# tick-mk-4_6_5.net
KiCad netlist of a schematic drawn in EAGLE
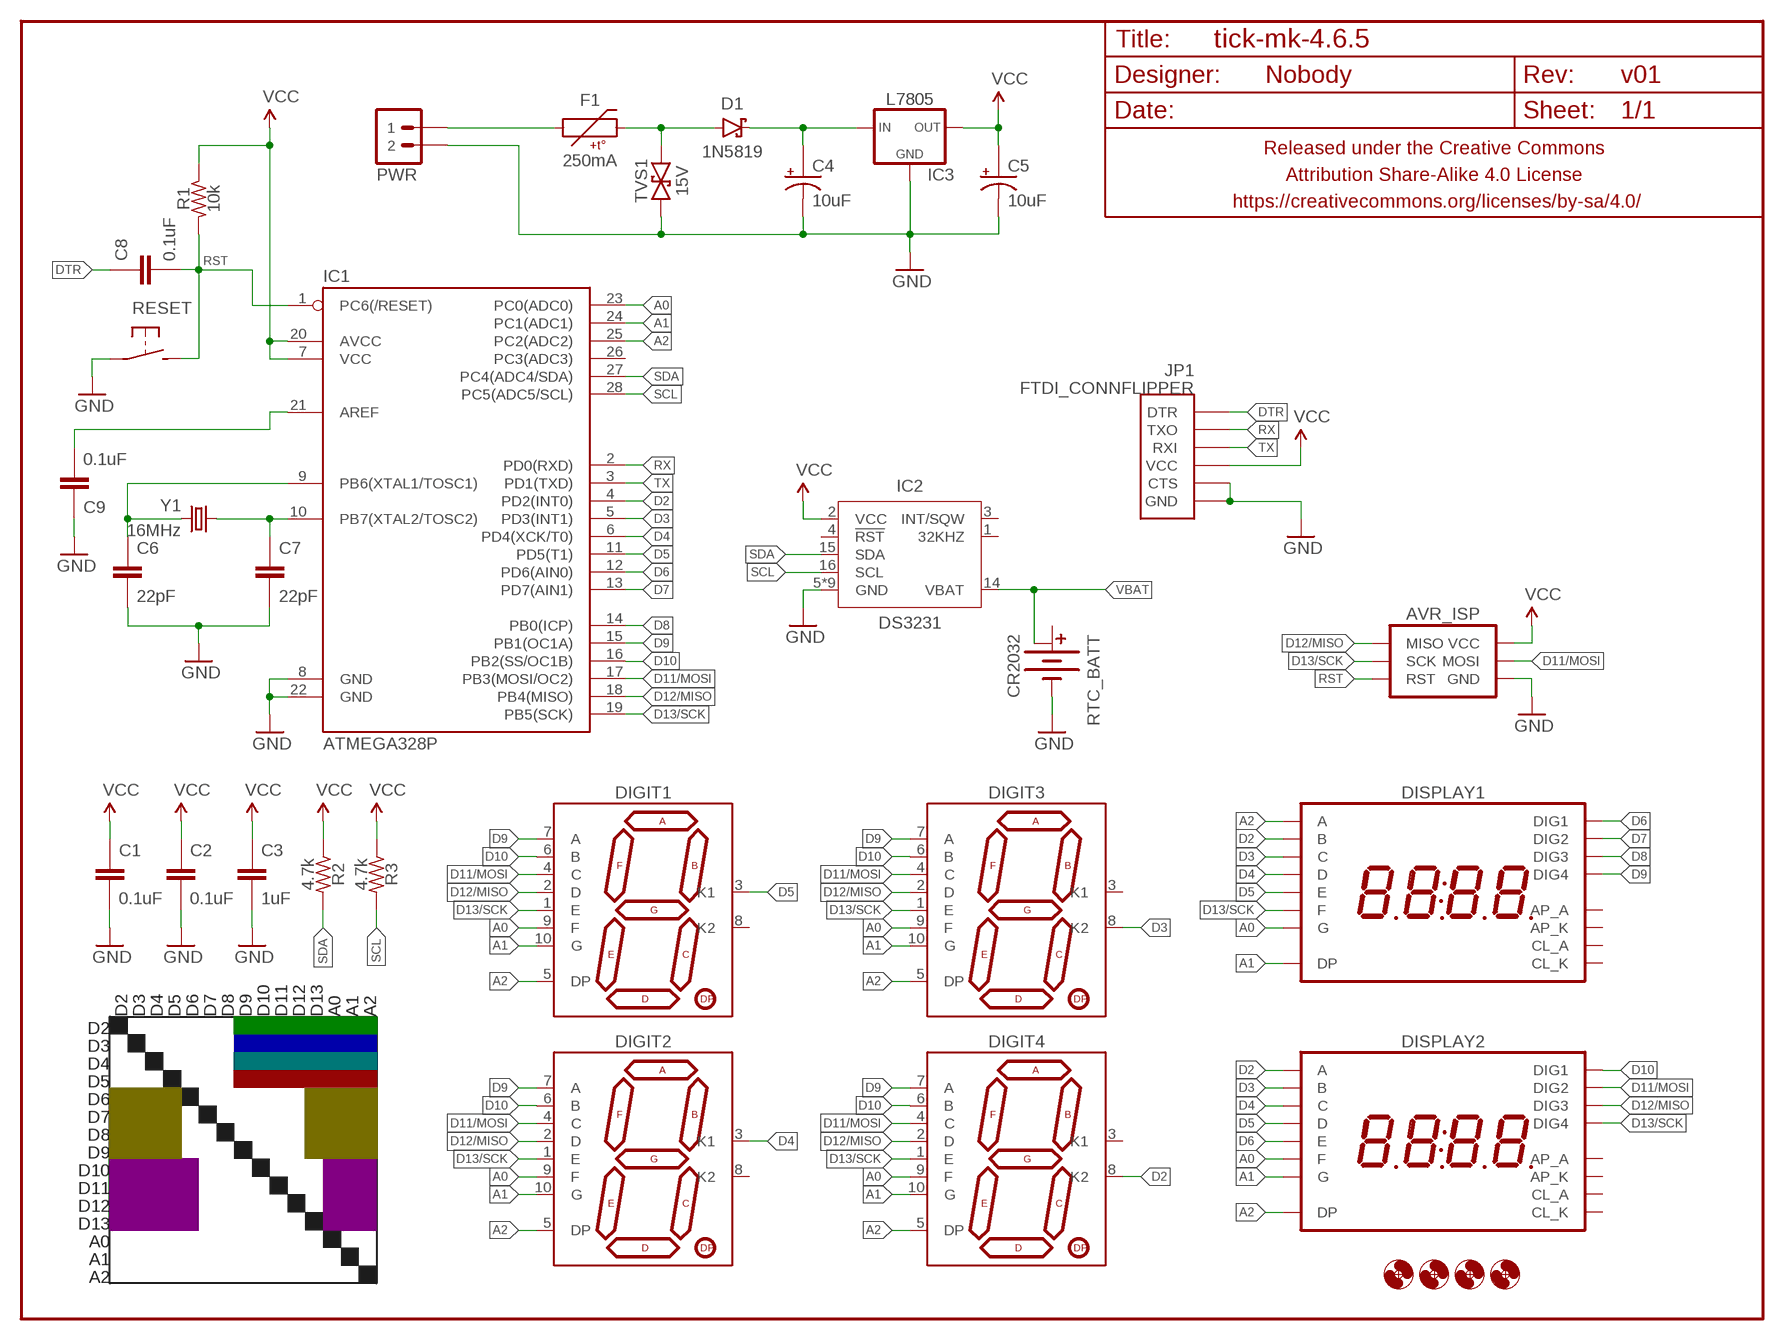
[diagram p0: schematic, sheet 1]

(export (version "E")
  (design (tool "Eeschema 10.0.6"))
  (components
    (comp (ref "AVR_ISP")
      (value "AVR_SPI_PRG_6PTH")
      (footprint "eagle-import:2X3")
      (libsource (lib "eagle-import") (part "AVR_SPI_PRG_6PTH"))
    )
    (comp (ref "C1")
      (value "0.1uF")
      (footprint "eagle-import:C025-024X044")
      (libsource (lib "eagle-import") (part "CAPACITOR-CERAMIC025-024X044"))
    )
    (comp (ref "C2")
      (value "0.1uF")
      (footprint "eagle-import:C025-024X044")
      (libsource (lib "eagle-import") (part "CAPACITOR-CERAMIC025-024X044"))
    )
    (comp (ref "C3")
      (value "1uF")
      (footprint "eagle-import:C025-024X044")
      (libsource (lib "eagle-import") (part "CAPACITOR-CERAMIC025-024X044"))
    )
    (comp (ref "C4")
      (value "10uF")
      (footprint "eagle-import:E2-5")
      (libsource (lib "eagle-import") (part "CAPACITOR-POLARIZEDE2-5"))
    )
    (comp (ref "C5")
      (value "10uF")
      (footprint "eagle-import:E2-5")
      (libsource (lib "eagle-import") (part "CAPACITOR-POLARIZEDE2-5"))
    )
    (comp (ref "C6")
      (value "22pF")
      (footprint "eagle-import:C025-024X044")
      (libsource (lib "eagle-import") (part "CAPACITOR-CERAMIC025-024X044"))
    )
    (comp (ref "C7")
      (value "22pF")
      (footprint "eagle-import:C025-024X044")
      (libsource (lib "eagle-import") (part "CAPACITOR-CERAMIC025-024X044"))
    )
    (comp (ref "C8")
      (value "0.1uF")
      (footprint "eagle-import:C025-024X044")
      (libsource (lib "eagle-import") (part "CAPACITOR-CERAMIC025-024X044"))
    )
    (comp (ref "C9")
      (value "0.1uF")
      (footprint "eagle-import:C025-024X044")
      (libsource (lib "eagle-import") (part "CAPACITOR-CERAMIC025-024X044"))
    )
    (comp (ref "D1")
      (value "1N5819")
      (footprint "eagle-import:DIODE-10.16MM")
      (libsource (lib "eagle-import") (part "DIODE-SCHOTTKYPTH-10.16MM"))
    )
    (comp (ref "DIGIT1")
      (value "7SEG_1DIGPTH-25.4MM-BARE")
      (footprint "eagle-import:7SEG_1DIG_25.4MM_NOSILK")
      (libsource (lib "eagle-import") (part "7SEG_1DIGPTH-25.4MM-BARE"))
    )
    (comp (ref "DIGIT2")
      (value "7SEG_1DIGPTH-25.4MM-BARE")
      (footprint "eagle-import:7SEG_1DIG_25.4MM_NOSILK")
      (libsource (lib "eagle-import") (part "7SEG_1DIGPTH-25.4MM-BARE"))
    )
    (comp (ref "DIGIT3")
      (value "7SEG_1DIGPTH-25.4MM-BARE")
      (footprint "eagle-import:7SEG_1DIG_25.4MM_NOSILK")
      (libsource (lib "eagle-import") (part "7SEG_1DIGPTH-25.4MM-BARE"))
    )
    (comp (ref "DIGIT4")
      (value "7SEG_1DIGPTH-25.4MM-BARE")
      (footprint "eagle-import:7SEG_1DIG_25.4MM_NOSILK")
      (libsource (lib "eagle-import") (part "7SEG_1DIGPTH-25.4MM-BARE"))
    )
    (comp (ref "DISPLAY1")
      (value "7SEG_4DIGIT_COLON_APOS")
      (footprint "eagle-import:7SEG_4DIG_10MM")
      (libsource (lib "eagle-import") (part "7SEG_4DIGIT_COLON_APOS"))
    )
    (comp (ref "DISPLAY2")
      (value "7SEG_4DIGIT_COLON_APOS")
      (footprint "eagle-import:7SEG_4DIG_10MM")
      (libsource (lib "eagle-import") (part "7SEG_4DIGIT_COLON_APOS"))
    )
    (comp (ref "F1")
      (value "250mA")
      (footprint "eagle-import:PTC-PTH-5.08MM")
      (libsource (lib "eagle-import") (part "PTCPTH-5.08MM"))
    )
    (comp (ref "FRAME1")
      (value "FRAME-LETTERNO_PACKAGE")
      (footprint "eagle-import:DUMMY")
      (fields (field (name "DESIGNER") "Nobody"))
      (libsource (lib "eagle-import") (part "FRAME-LETTERNO_PACKAGE"))
    )
    (comp (ref "H1")
      (value "HOLE#2")
      (footprint "eagle-import:HOLE-#2")
      (libsource (lib "eagle-import") (part "HOLE#2"))
    )
    (comp (ref "H2")
      (value "HOLE#2")
      (footprint "eagle-import:HOLE-#2")
      (libsource (lib "eagle-import") (part "HOLE#2"))
    )
    (comp (ref "H3")
      (value "HOLE#2")
      (footprint "eagle-import:HOLE-#2")
      (libsource (lib "eagle-import") (part "HOLE#2"))
    )
    (comp (ref "H4")
      (value "HOLE#2")
      (footprint "eagle-import:HOLE-#2")
      (libsource (lib "eagle-import") (part "HOLE#2"))
    )
    (comp (ref "IC1")
      (value "ATMEGA328P")
      (footprint "eagle-import:DIL28-3")
      (libsource (lib "eagle-import") (part "ATMEGA328P_PDIP"))
    )
    (comp (ref "IC2")
      (value "DS3231")
      (footprint "eagle-import:SO16W")
      (libsource (lib "eagle-import") (part "DS3231"))
    )
    (comp (ref "IC3")
      (value "L7805")
      (footprint "eagle-import:TO220-IGO-THERMPAD")
      (libsource (lib "eagle-import") (part "V_REG_78XXTO-220-THERMPAD"))
    )
    (comp (ref "JP1")
      (value "FTDI_CONNFLIPPER")
      (footprint "eagle-import:FTDI_CONN_FLIP")
      (libsource (lib "eagle-import") (part "FTDI_CONNFLIPPER"))
    )
    (comp (ref "PWR")
      (value "M02JST-PTH-VERT")
      (footprint "eagle-import:JST-2-PH-VERT-PTH")
      (libsource (lib "eagle-import") (part "M02JST-PTH-VERT"))
    )
    (comp (ref "R1")
      (value "10k")
      (footprint "eagle-import:RESISTOR-AXIAL-PTH-7.62MM")
      (libsource (lib "eagle-import") (part "RESISTORPTH-AXIAL-7.62MM"))
    )
    (comp (ref "R2")
      (value "4.7k")
      (footprint "eagle-import:RESISTOR-AXIAL-PTH-6.35MM")
      (libsource (lib "eagle-import") (part "RESISTORPTH-AXIAL-6.35MM"))
    )
    (comp (ref "R3")
      (value "4.7k")
      (footprint "eagle-import:RESISTOR-AXIAL-PTH-6.35MM")
      (libsource (lib "eagle-import") (part "RESISTORPTH-AXIAL-6.35MM"))
    )
    (comp (ref "RESET")
      (value "SPST-NO-TACT3MM-RA")
      (footprint "eagle-import:TACTILE-PTH-SIDE")
      (libsource (lib "eagle-import") (part "SPST-NO-TACT3MM-RA"))
    )
    (comp (ref "RTC_BATT")
      (value "CR2032")
      (footprint "eagle-import:BATTCON_20MM_MINE")
      (libsource (lib "eagle-import") (part "BATTERY-COINCR2032_SMD"))
    )
    (comp (ref "TVS1")
      (value "15V")
      (footprint "eagle-import:DO-41-TVS-BI-10.16MM")
      (libsource (lib "eagle-import") (part "TVSDO-41-10.16MM"))
    )
    (comp (ref "Y1")
      (value "16MHz")
      (footprint "eagle-import:HC49U-V")
      (libsource (lib "eagle-import") (part "CRYSTALHC49UV"))
    )
  )
  (nets
    (net (code "1") (name "A0") (class "Default")
      (node (ref "DIGIT1") (pin "9") (pinfunction "F_9") (pintype "bidirectional"))
      (node (ref "DIGIT2") (pin "9") (pinfunction "F_9") (pintype "bidirectional"))
      (node (ref "DIGIT3") (pin "9") (pinfunction "F_9") (pintype "bidirectional"))
      (node (ref "DIGIT4") (pin "9") (pinfunction "F_9") (pintype "bidirectional"))
      (node (ref "DISPLAY1") (pin "15") (pinfunction "G_15") (pintype "passive"))
      (node (ref "DISPLAY2") (pin "11") (pinfunction "F_11") (pintype "passive"))
      (node (ref "IC1") (pin "23") (pinfunction "PC0(ADC0)_23") (pintype "bidirectional"))
    )
    (net (code "2") (name "A1") (class "Default")
      (node (ref "DIGIT1") (pin "10") (pinfunction "G_10") (pintype "bidirectional"))
      (node (ref "DIGIT2") (pin "10") (pinfunction "G_10") (pintype "bidirectional"))
      (node (ref "DIGIT3") (pin "10") (pinfunction "G_10") (pintype "bidirectional"))
      (node (ref "DIGIT4") (pin "10") (pinfunction "G_10") (pintype "bidirectional"))
      (node (ref "DISPLAY1") (pin "7") (pinfunction "DP_7") (pintype "passive"))
      (node (ref "DISPLAY2") (pin "15") (pinfunction "G_15") (pintype "passive"))
      (node (ref "IC1") (pin "24") (pinfunction "PC1(ADC1)_24") (pintype "bidirectional"))
    )
    (net (code "3") (name "A2") (class "Default")
      (node (ref "DIGIT1") (pin "5") (pinfunction "DP_5") (pintype "bidirectional"))
      (node (ref "DIGIT2") (pin "5") (pinfunction "DP_5") (pintype "bidirectional"))
      (node (ref "DIGIT3") (pin "5") (pinfunction "DP_5") (pintype "bidirectional"))
      (node (ref "DIGIT4") (pin "5") (pinfunction "DP_5") (pintype "bidirectional"))
      (node (ref "DISPLAY1") (pin "14") (pinfunction "A_14") (pintype "passive"))
      (node (ref "DISPLAY2") (pin "7") (pinfunction "DP_7") (pintype "passive"))
      (node (ref "IC1") (pin "25") (pinfunction "PC2(ADC2)_25") (pintype "bidirectional"))
    )
    (net (code "4") (name "D2") (class "Default")
      (node (ref "DIGIT4") (pin "8") (pinfunction "K2_8") (pintype "bidirectional"))
      (node (ref "DISPLAY1") (pin "16") (pinfunction "B_16") (pintype "passive"))
      (node (ref "DISPLAY2") (pin "14") (pinfunction "A_14") (pintype "passive"))
      (node (ref "IC1") (pin "4") (pinfunction "PD2(INT0)_4") (pintype "bidirectional"))
    )
    (net (code "5") (name "D3") (class "Default")
      (node (ref "DIGIT3") (pin "8") (pinfunction "K2_8") (pintype "bidirectional"))
      (node (ref "DISPLAY1") (pin "13") (pinfunction "C_13") (pintype "passive"))
      (node (ref "DISPLAY2") (pin "16") (pinfunction "B_16") (pintype "passive"))
      (node (ref "IC1") (pin "5") (pinfunction "PD3(INT1)_5") (pintype "bidirectional"))
    )
    (net (code "6") (name "D4") (class "Default")
      (node (ref "DIGIT2") (pin "3") (pinfunction "K1_3") (pintype "bidirectional"))
      (node (ref "DISPLAY1") (pin "3") (pinfunction "D_3") (pintype "passive"))
      (node (ref "DISPLAY2") (pin "13") (pinfunction "C_13") (pintype "passive"))
      (node (ref "IC1") (pin "6") (pinfunction "PD4(XCK/T0)_6") (pintype "bidirectional"))
    )
    (net (code "7") (name "D5") (class "Default")
      (node (ref "DIGIT1") (pin "3") (pinfunction "K1_3") (pintype "bidirectional"))
      (node (ref "DISPLAY1") (pin "5") (pinfunction "E_5") (pintype "passive"))
      (node (ref "DISPLAY2") (pin "3") (pinfunction "D_3") (pintype "passive"))
      (node (ref "IC1") (pin "11") (pinfunction "PD5(T1)_11") (pintype "bidirectional"))
    )
    (net (code "8") (name "D6") (class "Default")
      (node (ref "DISPLAY1") (pin "1") (pinfunction "DIG1_1") (pintype "passive"))
      (node (ref "DISPLAY2") (pin "5") (pinfunction "E_5") (pintype "passive"))
      (node (ref "IC1") (pin "12") (pinfunction "PD6(AIN0)_12") (pintype "bidirectional"))
    )
    (net (code "9") (name "D7") (class "Default")
      (node (ref "DISPLAY1") (pin "2") (pinfunction "DIG2_2") (pintype "passive"))
      (node (ref "IC1") (pin "13") (pinfunction "PD7(AIN1)_13") (pintype "bidirectional"))
    )
    (net (code "10") (name "D8") (class "Default")
      (node (ref "DISPLAY1") (pin "6") (pinfunction "DIG3_6") (pintype "passive"))
      (node (ref "IC1") (pin "14") (pinfunction "PB0(ICP)_14") (pintype "bidirectional"))
    )
    (net (code "11") (name "D9") (class "Default")
      (node (ref "DIGIT1") (pin "7") (pinfunction "A_7") (pintype "bidirectional"))
      (node (ref "DIGIT2") (pin "7") (pinfunction "A_7") (pintype "bidirectional"))
      (node (ref "DIGIT3") (pin "7") (pinfunction "A_7") (pintype "bidirectional"))
      (node (ref "DIGIT4") (pin "7") (pinfunction "A_7") (pintype "bidirectional"))
      (node (ref "DISPLAY1") (pin "8") (pinfunction "DIG4_8") (pintype "passive"))
      (node (ref "IC1") (pin "15") (pinfunction "PB1(OC1A)_15") (pintype "bidirectional"))
    )
    (net (code "12") (name "D10") (class "Default")
      (node (ref "DIGIT1") (pin "6") (pinfunction "B_6") (pintype "bidirectional"))
      (node (ref "DIGIT2") (pin "6") (pinfunction "B_6") (pintype "bidirectional"))
      (node (ref "DIGIT3") (pin "6") (pinfunction "B_6") (pintype "bidirectional"))
      (node (ref "DIGIT4") (pin "6") (pinfunction "B_6") (pintype "bidirectional"))
      (node (ref "DISPLAY2") (pin "1") (pinfunction "DIG1_1") (pintype "passive"))
      (node (ref "IC1") (pin "16") (pinfunction "PB2(SS/OC1B)_16") (pintype "bidirectional"))
    )
    (net (code "13") (name "D11{slash}MOSI") (class "Default")
      (node (ref "AVR_ISP") (pin "4") (pinfunction "MOSI_4") (pintype "passive"))
      (node (ref "DIGIT1") (pin "4") (pinfunction "C_4") (pintype "bidirectional"))
      (node (ref "DIGIT2") (pin "4") (pinfunction "C_4") (pintype "bidirectional"))
      (node (ref "DIGIT3") (pin "4") (pinfunction "C_4") (pintype "bidirectional"))
      (node (ref "DIGIT4") (pin "4") (pinfunction "C_4") (pintype "bidirectional"))
      (node (ref "DISPLAY2") (pin "2") (pinfunction "DIG2_2") (pintype "passive"))
      (node (ref "IC1") (pin "17") (pinfunction "PB3(MOSI/OC2)_17") (pintype "bidirectional"))
    )
    (net (code "14") (name "D12{slash}MISO") (class "Default")
      (node (ref "AVR_ISP") (pin "1") (pinfunction "MISO_1") (pintype "passive"))
      (node (ref "DIGIT1") (pin "2") (pinfunction "D_2") (pintype "bidirectional"))
      (node (ref "DIGIT2") (pin "2") (pinfunction "D_2") (pintype "bidirectional"))
      (node (ref "DIGIT3") (pin "2") (pinfunction "D_2") (pintype "bidirectional"))
      (node (ref "DIGIT4") (pin "2") (pinfunction "D_2") (pintype "bidirectional"))
      (node (ref "DISPLAY2") (pin "6") (pinfunction "DIG3_6") (pintype "passive"))
      (node (ref "IC1") (pin "18") (pinfunction "PB4(MISO)_18") (pintype "bidirectional"))
    )
    (net (code "15") (name "D13{slash}SCK") (class "Default")
      (node (ref "AVR_ISP") (pin "3") (pinfunction "SCK_3") (pintype "passive"))
      (node (ref "DIGIT1") (pin "1") (pinfunction "E_1") (pintype "bidirectional"))
      (node (ref "DIGIT2") (pin "1") (pinfunction "E_1") (pintype "bidirectional"))
      (node (ref "DIGIT3") (pin "1") (pinfunction "E_1") (pintype "bidirectional"))
      (node (ref "DIGIT4") (pin "1") (pinfunction "E_1") (pintype "bidirectional"))
      (node (ref "DISPLAY1") (pin "11") (pinfunction "F_11") (pintype "passive"))
      (node (ref "DISPLAY2") (pin "8") (pinfunction "DIG4_8") (pintype "passive"))
      (node (ref "IC1") (pin "19") (pinfunction "PB5(SCK)_19") (pintype "bidirectional"))
    )
    (net (code "16") (name "DTR") (class "Default")
      (node (ref "C8") (pin "1") (pinfunction "1_1") (pintype "passive"))
      (node (ref "JP1") (pin "DTR") (pinfunction "DTR_DTR") (pintype "bidirectional"))
    )
    (net (code "17") (name "GND") (class "Default")
      (node (ref "AVR_ISP") (pin "6") (pinfunction "GND_6") (pintype "passive"))
      (node (ref "C1") (pin "2") (pinfunction "2_2") (pintype "passive"))
      (node (ref "C2") (pin "2") (pinfunction "2_2") (pintype "passive"))
      (node (ref "C3") (pin "2") (pinfunction "2_2") (pintype "passive"))
      (node (ref "C4") (pin "-") (pinfunction "-_-") (pintype "passive"))
      (node (ref "C5") (pin "-") (pinfunction "-_-") (pintype "passive"))
      (node (ref "C6") (pin "2") (pinfunction "2_2") (pintype "passive"))
      (node (ref "C7") (pin "2") (pinfunction "2_2") (pintype "passive"))
      (node (ref "C9") (pin "1") (pinfunction "1_1") (pintype "passive"))
      (node (ref "IC1") (pin "22") (pinfunction "GND_22") (pintype "bidirectional"))
      (node (ref "IC1") (pin "8") (pinfunction "GND_8") (pintype "bidirectional"))
      (node (ref "IC2") (pin "10") (pinfunction "GND_10") (pintype "bidirectional"))
      (node (ref "IC2") (pin "11") (pinfunction "GND_11") (pintype "bidirectional"))
      (node (ref "IC2") (pin "12") (pinfunction "GND_12") (pintype "bidirectional"))
      (node (ref "IC2") (pin "13") (pinfunction "GND_13") (pintype "bidirectional"))
      (node (ref "IC2") (pin "5") (pinfunction "GND_5") (pintype "bidirectional"))
      (node (ref "IC2") (pin "6") (pinfunction "GND_6") (pintype "bidirectional"))
      (node (ref "IC2") (pin "7") (pinfunction "GND_7") (pintype "bidirectional"))
      (node (ref "IC2") (pin "8") (pinfunction "GND_8") (pintype "bidirectional"))
      (node (ref "IC2") (pin "9") (pinfunction "GND_9") (pintype "bidirectional"))
      (node (ref "IC3") (pin "4") (pinfunction "GND_4") (pintype "bidirectional"))
      (node (ref "IC3") (pin "GND") (pinfunction "GND_GND") (pintype "bidirectional"))
      (node (ref "JP1") (pin "CTS") (pinfunction "CTS_CTS") (pintype "bidirectional"))
      (node (ref "JP1") (pin "GND") (pinfunction "GND_GND") (pintype "bidirectional"))
      (node (ref "PWR") (pin "2") (pinfunction "2_2") (pintype "passive"))
      (node (ref "RESET") (pin "1") (pinfunction "1_1") (pintype "passive"))
      (node (ref "RTC_BATT") (pin "BOTTOM") (pinfunction "-_BOTTOM") (pintype "bidirectional"))
      (node (ref "TVS1") (pin "P$1") (pinfunction "1_P$1") (pintype "passive"))
    )
    (net (code "18") (name "Net-(C4-Pad+)") (class "Default")
      (node (ref "C4") (pin "+") (pinfunction "+_+") (pintype "passive"))
      (node (ref "D1") (pin "C") (pinfunction "C_C") (pintype "passive"))
      (node (ref "IC3") (pin "IN") (pinfunction "IN_IN") (pintype "bidirectional"))
    )
    (net (code "19") (name "Net-(F1-1)") (class "Default")
      (node (ref "F1") (pin "P$1") (pinfunction "1_P$1") (pintype "passive"))
      (node (ref "PWR") (pin "1") (pinfunction "1_1") (pintype "passive"))
    )
    (net (code "20") (name "Net-(F1-2)") (class "Default")
      (node (ref "D1") (pin "A") (pinfunction "A_A") (pintype "passive"))
      (node (ref "F1") (pin "P$2") (pinfunction "2_P$2") (pintype "passive"))
      (node (ref "TVS1") (pin "P$2") (pinfunction "2_P$2") (pintype "passive"))
    )
    (net (code "21") (name "Net-(IC1-AREF)") (class "Default")
      (node (ref "C9") (pin "2") (pinfunction "2_2") (pintype "passive"))
      (node (ref "IC1") (pin "21") (pinfunction "AREF_21") (pintype "bidirectional"))
    )
    (net (code "22") (name "Net-(IC1-PB6(XTAL1{slash}TOSC1))") (class "Default")
      (node (ref "C6") (pin "1") (pinfunction "1_1") (pintype "passive"))
      (node (ref "IC1") (pin "9") (pinfunction "PB6(XTAL1/TOSC1)_9") (pintype "bidirectional"))
      (node (ref "Y1") (pin "2") (pinfunction "2_2") (pintype "passive"))
    )
    (net (code "23") (name "Net-(IC1-PB7(XTAL2{slash}TOSC2))") (class "Default")
      (node (ref "C7") (pin "1") (pinfunction "1_1") (pintype "passive"))
      (node (ref "IC1") (pin "10") (pinfunction "PB7(XTAL2/TOSC2)_10") (pintype "bidirectional"))
      (node (ref "Y1") (pin "1") (pinfunction "1_1") (pintype "passive"))
    )
    (net (code "24") (name "RST") (class "Default")
      (node (ref "AVR_ISP") (pin "5") (pinfunction "RST_5") (pintype "passive"))
      (node (ref "C8") (pin "2") (pinfunction "2_2") (pintype "passive"))
      (node (ref "IC1") (pin "1") (pinfunction "PC6(/RESET)_1") (pintype "bidirectional"))
      (node (ref "R1") (pin "P$2") (pinfunction "2_P$2") (pintype "passive"))
      (node (ref "RESET") (pin "2") (pinfunction "2_2") (pintype "passive"))
    )
    (net (code "25") (name "RX") (class "Default")
      (node (ref "IC1") (pin "2") (pinfunction "PD0(RXD)_2") (pintype "bidirectional"))
      (node (ref "JP1") (pin "TXO") (pinfunction "TXO_TXO") (pintype "bidirectional"))
    )
    (net (code "26") (name "SCL") (class "Default")
      (node (ref "IC1") (pin "28") (pinfunction "PC5(ADC5/SCL)_28") (pintype "bidirectional"))
      (node (ref "IC2") (pin "16") (pinfunction "SCL_16") (pintype "bidirectional"))
      (node (ref "R3") (pin "P$2") (pinfunction "2_P$2") (pintype "passive"))
    )
    (net (code "27") (name "SDA") (class "Default")
      (node (ref "IC1") (pin "27") (pinfunction "PC4(ADC4/SDA)_27") (pintype "bidirectional"))
      (node (ref "IC2") (pin "15") (pinfunction "SDA_15") (pintype "bidirectional"))
      (node (ref "R2") (pin "P$2") (pinfunction "2_P$2") (pintype "passive"))
    )
    (net (code "28") (name "TX") (class "Default")
      (node (ref "IC1") (pin "3") (pinfunction "PD1(TXD)_3") (pintype "bidirectional"))
      (node (ref "JP1") (pin "RXI") (pinfunction "RXI_RXI") (pintype "bidirectional"))
    )
    (net (code "29") (name "VBAT") (class "Default")
      (node (ref "IC2") (pin "14") (pinfunction "VBAT_14") (pintype "bidirectional"))
      (node (ref "RTC_BATT") (pin "TOP@2") (pinfunction "+1_TOP@2") (pintype "bidirectional"))
    )
    (net (code "30") (name "VCC") (class "Default")
      (node (ref "AVR_ISP") (pin "2") (pinfunction "VCC_2") (pintype "passive"))
      (node (ref "C1") (pin "1") (pinfunction "1_1") (pintype "passive"))
      (node (ref "C2") (pin "1") (pinfunction "1_1") (pintype "passive"))
      (node (ref "C3") (pin "1") (pinfunction "1_1") (pintype "passive"))
      (node (ref "C5") (pin "+") (pinfunction "+_+") (pintype "passive"))
      (node (ref "IC1") (pin "20") (pinfunction "AVCC_20") (pintype "bidirectional"))
      (node (ref "IC1") (pin "7") (pinfunction "VCC_7") (pintype "bidirectional"))
      (node (ref "IC2") (pin "2") (pinfunction "VCC_2") (pintype "bidirectional"))
      (node (ref "IC3") (pin "OUT") (pinfunction "OUT_OUT") (pintype "bidirectional"))
      (node (ref "JP1") (pin "VCC") (pinfunction "VCC_VCC") (pintype "bidirectional"))
      (node (ref "R1") (pin "P$1") (pinfunction "1_P$1") (pintype "passive"))
      (node (ref "R2") (pin "P$1") (pinfunction "1_P$1") (pintype "passive"))
      (node (ref "R3") (pin "P$1") (pinfunction "1_P$1") (pintype "passive"))
    )
    (net (code "31") (name "unconnected-(DIGIT1-K2-Pad8)") (class "Default")
      (node (ref "DIGIT1") (pin "8") (pinfunction "K2_8") (pintype "bidirectional"))
    )
    (net (code "32") (name "unconnected-(DIGIT2-K2-Pad8)") (class "Default")
      (node (ref "DIGIT2") (pin "8") (pinfunction "K2_8") (pintype "bidirectional"))
    )
    (net (code "33") (name "unconnected-(DIGIT3-K1-Pad3)") (class "Default")
      (node (ref "DIGIT3") (pin "3") (pinfunction "K1_3") (pintype "bidirectional"))
    )
    (net (code "34") (name "unconnected-(DIGIT4-K1-Pad3)") (class "Default")
      (node (ref "DIGIT4") (pin "3") (pinfunction "K1_3") (pintype "bidirectional"))
    )
    (net (code "35") (name "unconnected-(DISPLAY1-AP_A-Pad10)") (class "Default")
      (node (ref "DISPLAY1") (pin "10") (pinfunction "AP_A_10") (pintype "bidirectional"))
    )
    (net (code "36") (name "unconnected-(DISPLAY1-AP_K-Pad9)") (class "Default")
      (node (ref "DISPLAY1") (pin "9") (pinfunction "AP_K_9") (pintype "bidirectional"))
    )
    (net (code "37") (name "unconnected-(DISPLAY1-CL_A-Pad4)") (class "Default")
      (node (ref "DISPLAY1") (pin "4") (pinfunction "CL_A_4") (pintype "passive"))
    )
    (net (code "38") (name "unconnected-(DISPLAY1-CL_K-Pad12)") (class "Default")
      (node (ref "DISPLAY1") (pin "12") (pinfunction "CL_K_12") (pintype "passive"))
    )
    (net (code "39") (name "unconnected-(DISPLAY2-AP_A-Pad10)") (class "Default")
      (node (ref "DISPLAY2") (pin "10") (pinfunction "AP_A_10") (pintype "bidirectional"))
    )
    (net (code "40") (name "unconnected-(DISPLAY2-AP_K-Pad9)") (class "Default")
      (node (ref "DISPLAY2") (pin "9") (pinfunction "AP_K_9") (pintype "bidirectional"))
    )
    (net (code "41") (name "unconnected-(DISPLAY2-CL_A-Pad4)") (class "Default")
      (node (ref "DISPLAY2") (pin "4") (pinfunction "CL_A_4") (pintype "passive"))
    )
    (net (code "42") (name "unconnected-(DISPLAY2-CL_K-Pad12)") (class "Default")
      (node (ref "DISPLAY2") (pin "12") (pinfunction "CL_K_12") (pintype "passive"))
    )
    (net (code "43") (name "unconnected-(IC1-PC3(ADC3)-Pad26)") (class "Default")
      (node (ref "IC1") (pin "26") (pinfunction "PC3(ADC3)_26") (pintype "bidirectional"))
    )
    (net (code "44") (name "unconnected-(IC2-32KHZ-Pad1)") (class "Default")
      (node (ref "IC2") (pin "1") (pinfunction "32KHZ_1") (pintype "bidirectional"))
    )
    (net (code "45") (name "unconnected-(IC2-INT{slash}SQW-Pad3)") (class "Default")
      (node (ref "IC2") (pin "3") (pinfunction "INT/SQW_3") (pintype "bidirectional"))
    )
    (net (code "46") (name "unconnected-(IC2-~{RST}-Pad4)") (class "Default")
      (node (ref "IC2") (pin "4") (pinfunction "~{RST}_4") (pintype "bidirectional"))
    )
    (net (code "47") (name "unconnected-(RTC_BATT-+-PadTOP@1)") (class "Default")
      (node (ref "RTC_BATT") (pin "TOP@1") (pinfunction "+_TOP@1") (pintype "bidirectional"))
    )
  )
)
